# PWM2DC.net
KiCad netlist of a schematic drawn in EAGLE
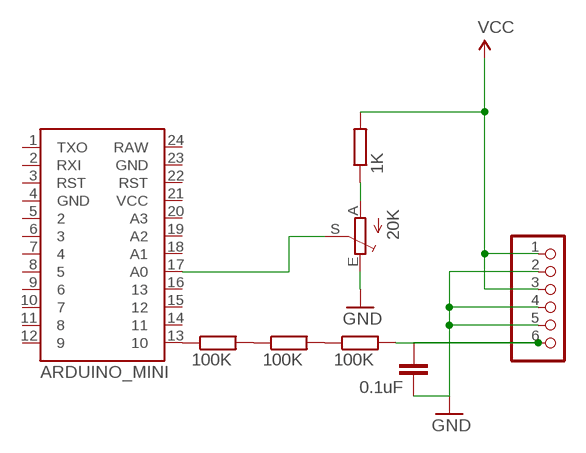
[diagram p0: schematic, sheet 1]

(export (version "E")
  (design (tool "Eeschema 10.0.6"))
  (components
    (comp (ref "C1")
      (value "0.1uF")
      (footprint "eagle-import:C050-025X075")
      (libsource (lib "eagle-import") (part "C-EU050-025X075"))
    )
    (comp (ref "JP1")
      (value "PINHD-1X6")
      (footprint "eagle-import:1X06")
      (libsource (lib "eagle-import") (part "PINHD-1X6"))
    )
    (comp (ref "R1")
      (value "100K")
      (footprint "eagle-import:0207_10")
      (libsource (lib "eagle-import") (part "R-EU_0207/10"))
    )
    (comp (ref "R2")
      (value "100K")
      (footprint "eagle-import:0207_10")
      (libsource (lib "eagle-import") (part "R-EU_0207/10"))
    )
    (comp (ref "R3")
      (value "100K")
      (footprint "eagle-import:0207_10")
      (libsource (lib "eagle-import") (part "R-EU_0207/10"))
    )
    (comp (ref "R4")
      (value "20K")
      (footprint "eagle-import:RJ9W")
      (libsource (lib "eagle-import") (part "TRIM_EU-RJ9W"))
    )
    (comp (ref "R5")
      (value "1K")
      (footprint "eagle-import:0207_10")
      (libsource (lib "eagle-import") (part "R-EU_0207/10"))
    )
    (comp (ref "U$1")
      (value "ARDUINO_MINI")
      (footprint "eagle-import:ARDUINO_MINI")
      (libsource (lib "eagle-import") (part "ARDUINO_MINI"))
    )
  )
  (nets
    (net (code "1") (name "GND") (class "Default")
      (node (ref "C1") (pin "1") (pinfunction "1_1") (pintype "passive"))
      (node (ref "JP1") (pin "2") (pinfunction "2_2") (pintype "passive"))
      (node (ref "JP1") (pin "4") (pinfunction "4_4") (pintype "passive"))
      (node (ref "JP1") (pin "5") (pinfunction "5_5") (pintype "passive"))
      (node (ref "R4") (pin "E") (pinfunction "E_E") (pintype "passive"))
    )
    (net (code "2") (name "Net-(C1-Pad2)") (class "Default")
      (node (ref "C1") (pin "2") (pinfunction "2_2") (pintype "passive"))
      (node (ref "JP1") (pin "6") (pinfunction "6_6") (pintype "passive"))
      (node (ref "R3") (pin "2") (pinfunction "2_2") (pintype "passive"))
    )
    (net (code "3") (name "Net-(R1-Pad2)") (class "Default")
      (node (ref "R1") (pin "2") (pinfunction "2_2") (pintype "passive"))
      (node (ref "R2") (pin "1") (pinfunction "1_1") (pintype "passive"))
    )
    (net (code "4") (name "Net-(R2-Pad2)") (class "Default")
      (node (ref "R2") (pin "2") (pinfunction "2_2") (pintype "passive"))
      (node (ref "R3") (pin "1") (pinfunction "1_1") (pintype "passive"))
    )
    (net (code "5") (name "Net-(R4-PadA)") (class "Default")
      (node (ref "R4") (pin "A") (pinfunction "A_A") (pintype "passive"))
      (node (ref "R5") (pin "1") (pinfunction "1_1") (pintype "passive"))
    )
    (net (code "6") (name "Net-(U$1-10)") (class "Default")
      (node (ref "R1") (pin "1") (pinfunction "1_1") (pintype "passive"))
      (node (ref "U$1") (pin "13") (pinfunction "10_13") (pintype "bidirectional"))
    )
    (net (code "7") (name "Net-(U$1-A0)") (class "Default")
      (node (ref "R4") (pin "S") (pinfunction "S_S") (pintype "passive"))
      (node (ref "U$1") (pin "17") (pinfunction "A0_17") (pintype "bidirectional"))
    )
    (net (code "8") (name "VCC") (class "Default")
      (node (ref "JP1") (pin "1") (pinfunction "1_1") (pintype "passive"))
      (node (ref "JP1") (pin "3") (pinfunction "3_3") (pintype "passive"))
      (node (ref "R5") (pin "2") (pinfunction "2_2") (pintype "passive"))
    )
    (net (code "9") (name "unconnected-(U$1-2-Pad5)") (class "Default")
      (node (ref "U$1") (pin "5") (pinfunction "2_5") (pintype "bidirectional"))
    )
    (net (code "10") (name "unconnected-(U$1-3-Pad6)") (class "Default")
      (node (ref "U$1") (pin "6") (pinfunction "3_6") (pintype "bidirectional"))
    )
    (net (code "11") (name "unconnected-(U$1-4-Pad7)") (class "Default")
      (node (ref "U$1") (pin "7") (pinfunction "4_7") (pintype "bidirectional"))
    )
    (net (code "12") (name "unconnected-(U$1-5-Pad8)") (class "Default")
      (node (ref "U$1") (pin "8") (pinfunction "5_8") (pintype "bidirectional"))
    )
    (net (code "13") (name "unconnected-(U$1-6-Pad9)") (class "Default")
      (node (ref "U$1") (pin "9") (pinfunction "6_9") (pintype "bidirectional"))
    )
    (net (code "14") (name "unconnected-(U$1-7-Pad10)") (class "Default")
      (node (ref "U$1") (pin "10") (pinfunction "7_10") (pintype "bidirectional"))
    )
    (net (code "15") (name "unconnected-(U$1-8-Pad11)") (class "Default")
      (node (ref "U$1") (pin "11") (pinfunction "8_11") (pintype "bidirectional"))
    )
    (net (code "16") (name "unconnected-(U$1-9-Pad12)") (class "Default")
      (node (ref "U$1") (pin "12") (pinfunction "9_12") (pintype "bidirectional"))
    )
    (net (code "17") (name "unconnected-(U$1-11-Pad14)") (class "Default")
      (node (ref "U$1") (pin "14") (pinfunction "11_14") (pintype "bidirectional"))
    )
    (net (code "18") (name "unconnected-(U$1-12-Pad15)") (class "Default")
      (node (ref "U$1") (pin "15") (pinfunction "12_15") (pintype "bidirectional"))
    )
    (net (code "19") (name "unconnected-(U$1-13-Pad16)") (class "Default")
      (node (ref "U$1") (pin "16") (pinfunction "13_16") (pintype "bidirectional"))
    )
    (net (code "20") (name "unconnected-(U$1-A1-Pad18)") (class "Default")
      (node (ref "U$1") (pin "18") (pinfunction "A1_18") (pintype "bidirectional"))
    )
    (net (code "21") (name "unconnected-(U$1-A2-Pad19)") (class "Default")
      (node (ref "U$1") (pin "19") (pinfunction "A2_19") (pintype "bidirectional"))
    )
    (net (code "22") (name "unconnected-(U$1-A3-Pad20)") (class "Default")
      (node (ref "U$1") (pin "20") (pinfunction "A3_20") (pintype "bidirectional"))
    )
    (net (code "23") (name "unconnected-(U$1-GND-Pad4)") (class "Default")
      (node (ref "U$1") (pin "4") (pinfunction "GND_4") (pintype "bidirectional"))
    )
    (net (code "24") (name "unconnected-(U$1-GND-Pad23)") (class "Default")
      (node (ref "U$1") (pin "23") (pinfunction "GND_23") (pintype "bidirectional"))
    )
    (net (code "25") (name "unconnected-(U$1-RAW-Pad24)") (class "Default")
      (node (ref "U$1") (pin "24") (pinfunction "RAW_24") (pintype "bidirectional"))
    )
    (net (code "26") (name "unconnected-(U$1-RST-Pad3)") (class "Default")
      (node (ref "U$1") (pin "3") (pinfunction "RST_3") (pintype "bidirectional"))
    )
    (net (code "27") (name "unconnected-(U$1-RST-Pad22)") (class "Default")
      (node (ref "U$1") (pin "22") (pinfunction "RST_22") (pintype "bidirectional"))
    )
    (net (code "28") (name "unconnected-(U$1-RXI-Pad2)") (class "Default")
      (node (ref "U$1") (pin "2") (pinfunction "RXI_2") (pintype "bidirectional"))
    )
    (net (code "29") (name "unconnected-(U$1-TXO-Pad1)") (class "Default")
      (node (ref "U$1") (pin "1") (pinfunction "TXO_1") (pintype "bidirectional"))
    )
    (net (code "30") (name "unconnected-(U$1-VCC-Pad21)") (class "Default")
      (node (ref "U$1") (pin "21") (pinfunction "VCC_21") (pintype "bidirectional"))
    )
  )
)
